# 002-main.net
KiCad netlist of a schematic drawn in EAGLE
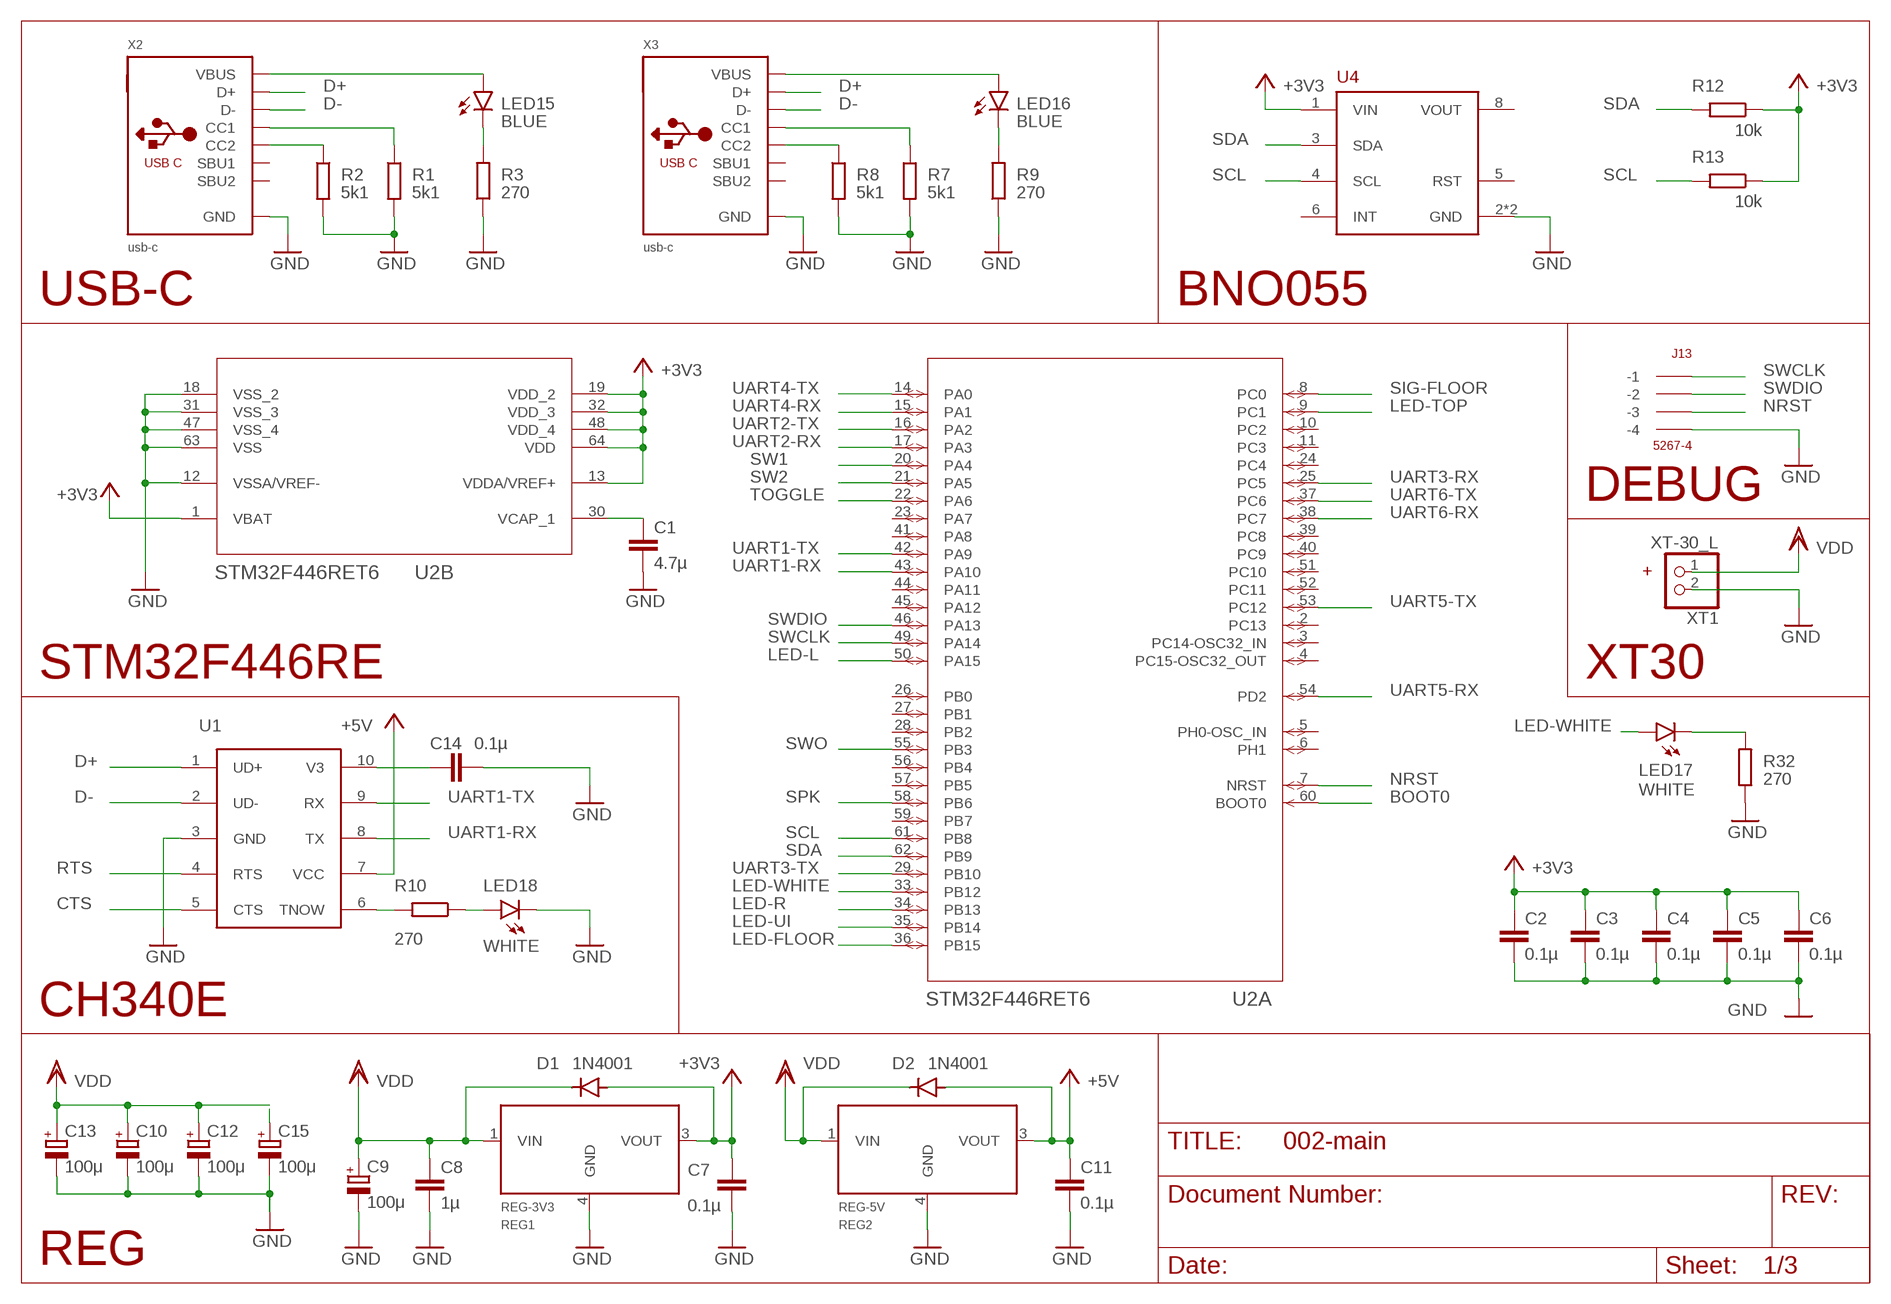
[diagram p0: schematic, sheet 1]
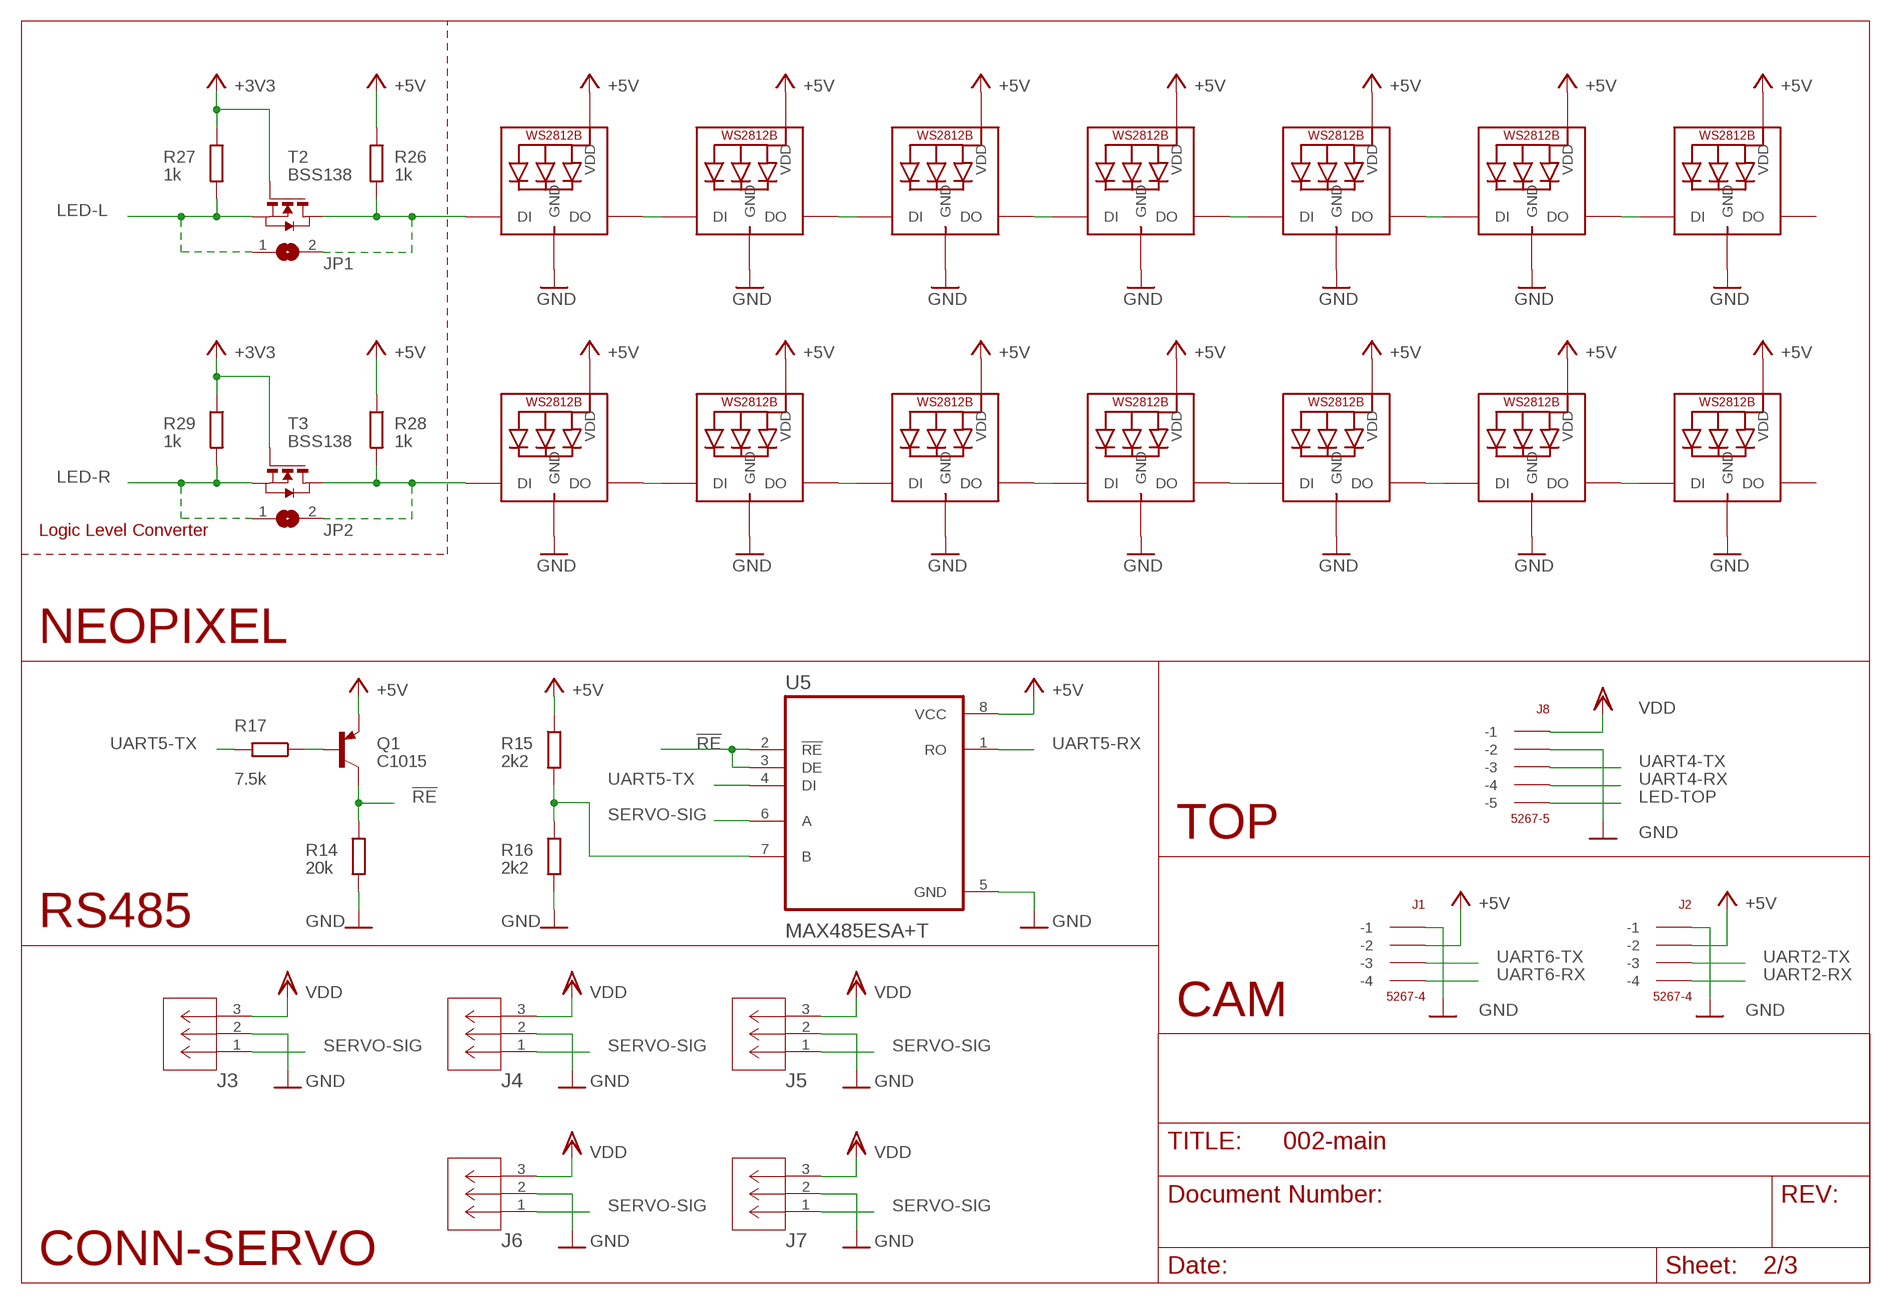
[diagram p1: schematic, sheet 2]
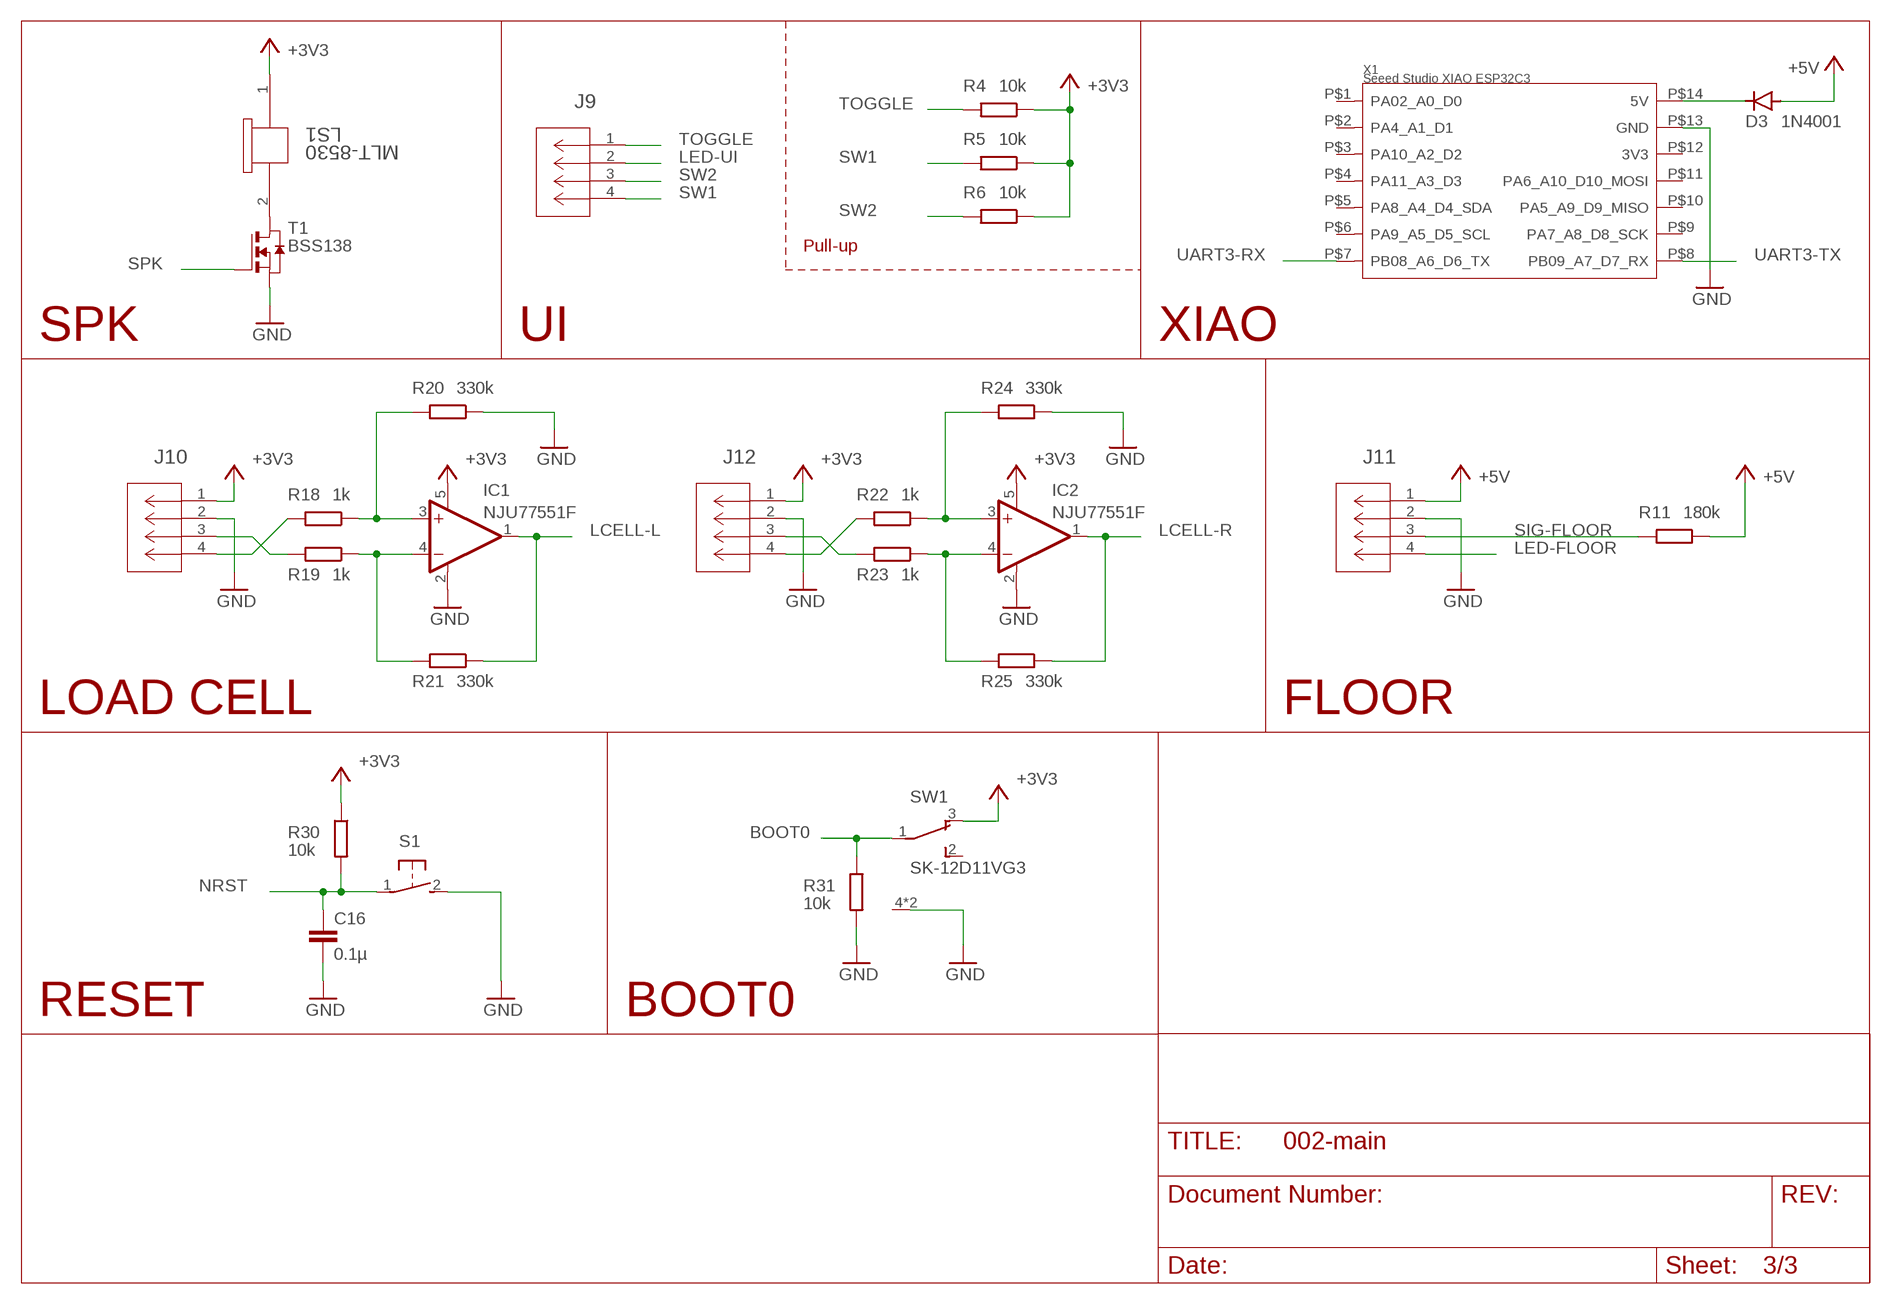
[diagram p2: schematic, sheet 3]

(export (version "E")
  (design (tool "Eeschema 10.0.6"))
  (components
    (comp (ref "C1")
      (value "4.7µ")
      (footprint "eagle-import:C0603")
      (libsource (lib "eagle-import") (part "C-EUC0603"))
    )
    (comp (ref "C2")
      (value "0.1µ")
      (footprint "eagle-import:C0603")
      (libsource (lib "eagle-import") (part "C-EUC0603"))
    )
    (comp (ref "C3")
      (value "0.1µ")
      (footprint "eagle-import:C0603")
      (libsource (lib "eagle-import") (part "C-EUC0603"))
    )
    (comp (ref "C4")
      (value "0.1µ")
      (footprint "eagle-import:C0603")
      (libsource (lib "eagle-import") (part "C-EUC0603"))
    )
    (comp (ref "C5")
      (value "0.1µ")
      (footprint "eagle-import:C0603")
      (libsource (lib "eagle-import") (part "C-EUC0603"))
    )
    (comp (ref "C6")
      (value "0.1µ")
      (footprint "eagle-import:C0603")
      (libsource (lib "eagle-import") (part "C-EUC0603"))
    )
    (comp (ref "C7")
      (value "0.1µ")
      (footprint "eagle-import:C0603")
      (libsource (lib "eagle-import") (part "C-EUC0603"))
    )
    (comp (ref "C8")
      (value "1µ")
      (footprint "eagle-import:C0603")
      (libsource (lib "eagle-import") (part "C-EUC0603"))
    )
    (comp (ref "C9")
      (value "100μ")
      (footprint "eagle-import:153CLV-0505")
      (libsource (lib "eagle-import") (part "CPOL-EU153CLV-0505"))
    )
    (comp (ref "C10")
      (value "100μ")
      (footprint "eagle-import:153CLV-0505")
      (libsource (lib "eagle-import") (part "CPOL-EU153CLV-0505"))
    )
    (comp (ref "C11")
      (value "0.1µ")
      (footprint "eagle-import:C0603")
      (libsource (lib "eagle-import") (part "C-EUC0603"))
    )
    (comp (ref "C12")
      (value "100μ")
      (footprint "eagle-import:153CLV-0505")
      (libsource (lib "eagle-import") (part "CPOL-EU153CLV-0505"))
    )
    (comp (ref "C13")
      (value "100μ")
      (footprint "eagle-import:153CLV-0505")
      (libsource (lib "eagle-import") (part "CPOL-EU153CLV-0505"))
    )
    (comp (ref "C14")
      (value "0.1µ")
      (footprint "eagle-import:C0603")
      (libsource (lib "eagle-import") (part "C-EUC0603"))
    )
    (comp (ref "C15")
      (value "100μ")
      (footprint "eagle-import:153CLV-0505")
      (libsource (lib "eagle-import") (part "CPOL-EU153CLV-0505"))
    )
    (comp (ref "D1")
      (value "1N4001")
      (footprint "eagle-import:SMA-DO214AC")
      (libsource (lib "eagle-import") (part "GF1"))
    )
    (comp (ref "D2")
      (value "1N4001")
      (footprint "eagle-import:SMA-DO214AC")
      (libsource (lib "eagle-import") (part "GF1"))
    )
    (comp (ref "J13")
      (value "5267-4")
      (footprint "eagle-import:5267-4")
      (libsource (lib "eagle-import") (part "5267-4"))
    )
    (comp (ref "LED15")
      (value "BLUE")
      (footprint "eagle-import:SML0603")
      (libsource (lib "eagle-import") (part "LEDSML0603"))
    )
    (comp (ref "LED16")
      (value "BLUE")
      (footprint "eagle-import:SML0603")
      (libsource (lib "eagle-import") (part "LEDSML0603"))
    )
    (comp (ref "LED17")
      (value "WHITE")
      (footprint "eagle-import:SML0603")
      (libsource (lib "eagle-import") (part "LEDSML0603"))
    )
    (comp (ref "LED18")
      (value "WHITE")
      (footprint "eagle-import:SML0603")
      (libsource (lib "eagle-import") (part "LEDSML0603"))
    )
    (comp (ref "R1")
      (value "5k1")
      (footprint "eagle-import:R0402")
      (libsource (lib "eagle-import") (part "R-EU_R0402"))
    )
    (comp (ref "R2")
      (value "5k1")
      (footprint "eagle-import:R0402")
      (libsource (lib "eagle-import") (part "R-EU_R0402"))
    )
    (comp (ref "R3")
      (value "270")
      (footprint "eagle-import:R0402")
      (libsource (lib "eagle-import") (part "R-EU_R0402"))
    )
    (comp (ref "R7")
      (value "5k1")
      (footprint "eagle-import:R0402")
      (libsource (lib "eagle-import") (part "R-EU_R0402"))
    )
    (comp (ref "R8")
      (value "5k1")
      (footprint "eagle-import:R0402")
      (libsource (lib "eagle-import") (part "R-EU_R0402"))
    )
    (comp (ref "R9")
      (value "270")
      (footprint "eagle-import:R0402")
      (libsource (lib "eagle-import") (part "R-EU_R0402"))
    )
    (comp (ref "R10")
      (value "270")
      (footprint "eagle-import:R0402")
      (libsource (lib "eagle-import") (part "R-EU_R0402"))
    )
    (comp (ref "R12")
      (value "10k")
      (footprint "eagle-import:R0402")
      (libsource (lib "eagle-import") (part "R-EU_R0402"))
    )
    (comp (ref "R13")
      (value "10k")
      (footprint "eagle-import:R0402")
      (libsource (lib "eagle-import") (part "R-EU_R0402"))
    )
    (comp (ref "R32")
      (value "270")
      (footprint "eagle-import:R0402")
      (libsource (lib "eagle-import") (part "R-EU_R0402"))
    )
    (comp (ref "REG1")
      (value "REG-3V3")
      (footprint "eagle-import:MYPARTS_D-PAK_TO252AA")
      (libsource (lib "eagle-import") (part "MYPARTS_NJM7800S-REGULATOR"))
    )
    (comp (ref "REG2")
      (value "REG-5V")
      (footprint "eagle-import:MYPARTS_D-PAK_TO252AA")
      (libsource (lib "eagle-import") (part "MYPARTS_NJM7800S-REGULATOR"))
    )
    (comp (ref "U1")
      (value "CH340ESMD")
      (footprint "eagle-import:MSOP10")
      (libsource (lib "eagle-import") (part "CH340ESMD"))
    )
    (comp (ref "U2")
      (value "STM32F446RET6")
      (footprint "eagle-import:LQFP64-10X10MM")
      (fields (field (name "COPYRIGHT") "Copyright (C) 2022 Ultra Librarian. All rights reserved."))
      (libsource (lib "eagle-import") (part "STM32F446RET6"))
    )
    (comp (ref "U4")
      (value "BNO055")
      (footprint "eagle-import:SOCKET-08")
      (libsource (lib "eagle-import") (part "BNO055"))
    )
    (comp (ref "X2")
      (value "usb-c")
      (footprint "eagle-import:USB_C_CUSB31-CFM2AX-01-X")
      (libsource (lib "eagle-import") (part "USB_C"))
    )
    (comp (ref "X3")
      (value "usb-c")
      (footprint "eagle-import:USB_C_CUSB31-CFM2AX-01-X")
      (libsource (lib "eagle-import") (part "USB_C"))
    )
    (comp (ref "XT1")
      (value "XT-30_L")
      (footprint "eagle-import:XT-30_L")
      (libsource (lib "eagle-import") (part "XT-30_L"))
    )
    (comp (ref "J1")
      (value "5267-4")
      (footprint "eagle-import:5267-4")
      (libsource (lib "eagle-import") (part "5267-4"))
    )
    (comp (ref "J2")
      (value "5267-4")
      (footprint "eagle-import:5267-4")
      (libsource (lib "eagle-import") (part "5267-4"))
    )
    (comp (ref "J3")
      (value "22057035")
      (footprint "eagle-import:CON_22057035_MOL")
      (fields (field (name "COPYRIGHT") "Copyright (C) 2022 Ultra Librarian. All rights reserved."))
      (libsource (lib "eagle-import") (part "22057035"))
    )
    (comp (ref "J4")
      (value "22057035")
      (footprint "eagle-import:CON_22057035_MOL")
      (fields (field (name "COPYRIGHT") "Copyright (C) 2022 Ultra Librarian. All rights reserved."))
      (libsource (lib "eagle-import") (part "22057035"))
    )
    (comp (ref "J5")
      (value "22057035")
      (footprint "eagle-import:CON_22057035_MOL")
      (fields (field (name "COPYRIGHT") "Copyright (C) 2022 Ultra Librarian. All rights reserved."))
      (libsource (lib "eagle-import") (part "22057035"))
    )
    (comp (ref "J6")
      (value "22057035")
      (footprint "eagle-import:CON_22057035_MOL")
      (fields (field (name "COPYRIGHT") "Copyright (C) 2022 Ultra Librarian. All rights reserved."))
      (libsource (lib "eagle-import") (part "22057035"))
    )
    (comp (ref "J7")
      (value "22057035")
      (footprint "eagle-import:CON_22057035_MOL")
      (fields (field (name "COPYRIGHT") "Copyright (C) 2022 Ultra Librarian. All rights reserved."))
      (libsource (lib "eagle-import") (part "22057035"))
    )
    (comp (ref "J8")
      (value "5267-5")
      (footprint "eagle-import:5267-5")
      (libsource (lib "eagle-import") (part "5267-5"))
    )
    (comp (ref "JP1")
      (value "JP2")
      (footprint "eagle-import:JP2")
      (libsource (lib "eagle-import") (part "JP2"))
    )
    (comp (ref "JP2")
      (value "JP2")
      (footprint "eagle-import:JP2")
      (libsource (lib "eagle-import") (part "JP2"))
    )
    (comp (ref "LED1")
      (value "WS2812B_2020")
      (footprint "eagle-import:WS2812B_2020")
      (libsource (lib "eagle-import") (part "WS2812B_2020"))
    )
    (comp (ref "LED2")
      (value "WS2812B_2020")
      (footprint "eagle-import:WS2812B_2020")
      (libsource (lib "eagle-import") (part "WS2812B_2020"))
    )
    (comp (ref "LED3")
      (value "WS2812B_2020")
      (footprint "eagle-import:WS2812B_2020")
      (libsource (lib "eagle-import") (part "WS2812B_2020"))
    )
    (comp (ref "LED4")
      (value "WS2812B_2020")
      (footprint "eagle-import:WS2812B_2020")
      (libsource (lib "eagle-import") (part "WS2812B_2020"))
    )
    (comp (ref "LED5")
      (value "WS2812B_2020")
      (footprint "eagle-import:WS2812B_2020")
      (libsource (lib "eagle-import") (part "WS2812B_2020"))
    )
    (comp (ref "LED6")
      (value "WS2812B_2020")
      (footprint "eagle-import:WS2812B_2020")
      (libsource (lib "eagle-import") (part "WS2812B_2020"))
    )
    (comp (ref "LED7")
      (value "WS2812B_2020")
      (footprint "eagle-import:WS2812B_2020")
      (libsource (lib "eagle-import") (part "WS2812B_2020"))
    )
    (comp (ref "LED8")
      (value "WS2812B_2020")
      (footprint "eagle-import:WS2812B_2020")
      (libsource (lib "eagle-import") (part "WS2812B_2020"))
    )
    (comp (ref "LED9")
      (value "WS2812B_2020")
      (footprint "eagle-import:WS2812B_2020")
      (libsource (lib "eagle-import") (part "WS2812B_2020"))
    )
    (comp (ref "LED10")
      (value "WS2812B_2020")
      (footprint "eagle-import:WS2812B_2020")
      (libsource (lib "eagle-import") (part "WS2812B_2020"))
    )
    (comp (ref "LED11")
      (value "WS2812B_2020")
      (footprint "eagle-import:WS2812B_2020")
      (libsource (lib "eagle-import") (part "WS2812B_2020"))
    )
    (comp (ref "LED12")
      (value "WS2812B_2020")
      (footprint "eagle-import:WS2812B_2020")
      (libsource (lib "eagle-import") (part "WS2812B_2020"))
    )
    (comp (ref "LED13")
      (value "WS2812B_2020")
      (footprint "eagle-import:WS2812B_2020")
      (libsource (lib "eagle-import") (part "WS2812B_2020"))
    )
    (comp (ref "LED14")
      (value "WS2812B_2020")
      (footprint "eagle-import:WS2812B_2020")
      (libsource (lib "eagle-import") (part "WS2812B_2020"))
    )
    (comp (ref "Q1")
      (value "C1015")
      (footprint "eagle-import:SOT23")
      (libsource (lib "eagle-import") (part "BCX71SMD"))
    )
    (comp (ref "R14")
      (value "20k")
      (footprint "eagle-import:R0402")
      (libsource (lib "eagle-import") (part "R-EU_R0402"))
    )
    (comp (ref "R15")
      (value "2k2")
      (footprint "eagle-import:R0402")
      (libsource (lib "eagle-import") (part "R-EU_R0402"))
    )
    (comp (ref "R16")
      (value "2k2")
      (footprint "eagle-import:R0402")
      (libsource (lib "eagle-import") (part "R-EU_R0402"))
    )
    (comp (ref "R17")
      (value "7.5k")
      (footprint "eagle-import:R0402")
      (libsource (lib "eagle-import") (part "R-EU_R0402"))
    )
    (comp (ref "R26")
      (value "1k")
      (footprint "eagle-import:R0402")
      (libsource (lib "eagle-import") (part "R-EU_R0402"))
    )
    (comp (ref "R27")
      (value "1k")
      (footprint "eagle-import:R0402")
      (libsource (lib "eagle-import") (part "R-EU_R0402"))
    )
    (comp (ref "R28")
      (value "1k")
      (footprint "eagle-import:R0402")
      (libsource (lib "eagle-import") (part "R-EU_R0402"))
    )
    (comp (ref "R29")
      (value "1k")
      (footprint "eagle-import:R0402")
      (libsource (lib "eagle-import") (part "R-EU_R0402"))
    )
    (comp (ref "T2")
      (value "BSS138")
      (footprint "eagle-import:SOT-23")
      (libsource (lib "eagle-import") (part "NMOSSOT23"))
    )
    (comp (ref "T3")
      (value "BSS138")
      (footprint "eagle-import:SOT-23")
      (libsource (lib "eagle-import") (part "NMOSSOT23"))
    )
    (comp (ref "U5")
      (value "MAX485ESA+T")
      (footprint "eagle-import:SOIC127P600X175-8N")
      (fields (field (name "MF") "Maxim Integrated") (field (name "MP") "MAX485ESA"))
      (libsource (lib "eagle-import") (part "MAX485ESA+T"))
    )
    (comp (ref "C16")
      (value "0.1µ")
      (footprint "eagle-import:C0603")
      (libsource (lib "eagle-import") (part "C-EUC0603"))
    )
    (comp (ref "D3")
      (value "1N4001")
      (footprint "eagle-import:SMA-DO214AC")
      (libsource (lib "eagle-import") (part "GF1"))
    )
    (comp (ref "IC1")
      (value "NJU77551F")
      (footprint "eagle-import:SOT23-5")
      (fields (field (name "MPN") "OPA340NA/3KG4"))
      (libsource (lib "eagle-import") (part "OPA340N"))
    )
    (comp (ref "IC2")
      (value "NJU77551F")
      (footprint "eagle-import:SOT23-5")
      (fields (field (name "MPN") "OPA340NA/3KG4"))
      (libsource (lib "eagle-import") (part "OPA340N"))
    )
    (comp (ref "J9")
      (value "22057045")
      (footprint "eagle-import:CON_22057045_MOL")
      (fields (field (name "COPYRIGHT") "Copyright (C) 2022 Ultra Librarian. All rights reserved."))
      (libsource (lib "eagle-import") (part "22057045"))
    )
    (comp (ref "J10")
      (value "22057045")
      (footprint "eagle-import:CON_22057045_MOL")
      (fields (field (name "COPYRIGHT") "Copyright (C) 2022 Ultra Librarian. All rights reserved."))
      (libsource (lib "eagle-import") (part "22057045"))
    )
    (comp (ref "J11")
      (value "22057045")
      (footprint "eagle-import:CON_22057045_MOL")
      (fields (field (name "COPYRIGHT") "Copyright (C) 2022 Ultra Librarian. All rights reserved."))
      (libsource (lib "eagle-import") (part "22057045"))
    )
    (comp (ref "J12")
      (value "22057045")
      (footprint "eagle-import:CON_22057045_MOL")
      (fields (field (name "COPYRIGHT") "Copyright (C) 2022 Ultra Librarian. All rights reserved."))
      (libsource (lib "eagle-import") (part "22057045"))
    )
    (comp (ref "LS1")
      (value "MLT-8530")
      (footprint "eagle-import:MLT-8530_JHE")
      (fields (field (name "COPYRIGHT") "Copyright (C) 2022 Ultra Librarian. All rights reserved."))
      (libsource (lib "eagle-import") (part "MLT-8530"))
    )
    (comp (ref "R4")
      (value "10k")
      (footprint "eagle-import:R0402")
      (libsource (lib "eagle-import") (part "R-EU_R0402"))
    )
    (comp (ref "R5")
      (value "10k")
      (footprint "eagle-import:R0402")
      (libsource (lib "eagle-import") (part "R-EU_R0402"))
    )
    (comp (ref "R6")
      (value "10k")
      (footprint "eagle-import:R0402")
      (libsource (lib "eagle-import") (part "R-EU_R0402"))
    )
    (comp (ref "R11")
      (value "180k")
      (footprint "eagle-import:R0402")
      (libsource (lib "eagle-import") (part "R-EU_R0402"))
    )
    (comp (ref "R18")
      (value "1k")
      (footprint "eagle-import:R0402")
      (libsource (lib "eagle-import") (part "R-EU_R0402"))
    )
    (comp (ref "R19")
      (value "1k")
      (footprint "eagle-import:R0402")
      (libsource (lib "eagle-import") (part "R-EU_R0402"))
    )
    (comp (ref "R20")
      (value "330k")
      (footprint "eagle-import:R0402")
      (libsource (lib "eagle-import") (part "R-EU_R0402"))
    )
    (comp (ref "R21")
      (value "330k")
      (footprint "eagle-import:R0402")
      (libsource (lib "eagle-import") (part "R-EU_R0402"))
    )
    (comp (ref "R22")
      (value "1k")
      (footprint "eagle-import:R0402")
      (libsource (lib "eagle-import") (part "R-EU_R0402"))
    )
    (comp (ref "R23")
      (value "1k")
      (footprint "eagle-import:R0402")
      (libsource (lib "eagle-import") (part "R-EU_R0402"))
    )
    (comp (ref "R24")
      (value "330k")
      (footprint "eagle-import:R0402")
      (libsource (lib "eagle-import") (part "R-EU_R0402"))
    )
    (comp (ref "R25")
      (value "330k")
      (footprint "eagle-import:R0402")
      (libsource (lib "eagle-import") (part "R-EU_R0402"))
    )
    (comp (ref "R30")
      (value "10k")
      (footprint "eagle-import:R0402")
      (libsource (lib "eagle-import") (part "R-EU_R0402"))
    )
    (comp (ref "R31")
      (value "10k")
      (footprint "eagle-import:R0402")
      (libsource (lib "eagle-import") (part "R-EU_R0402"))
    )
    (comp (ref "S1")
      (value "31-XX")
      (footprint "eagle-import:B3F-31XX")
      (fields (field (name "MPN") "B3F-3100"))
      (libsource (lib "eagle-import") (part "31-XX"))
    )
    (comp (ref "SW1")
      (value "SK-12D11VG3")
      (footprint "eagle-import:SK-12D11VG3")
      (libsource (lib "eagle-import") (part "SK-12D11VG3"))
    )
    (comp (ref "T1")
      (value "BSS138")
      (footprint "eagle-import:SOT-23")
      (libsource (lib "eagle-import") (part "NMOSSOT23"))
    )
    (comp (ref "X1")
      (value "Seeed Studio XIAO ESP32C3")
      (footprint "eagle-import:XIAO-PINHEAD")
      (libsource (lib "eagle-import") (part "SEEEDUINO-XIAO-DIP"))
    )
  )
  (nets
    (net (code "1") (name "+3V3") (class "Default")
      (node (ref "C2") (pin "1") (pinfunction "1_1") (pintype "passive"))
      (node (ref "C3") (pin "1") (pinfunction "1_1") (pintype "passive"))
      (node (ref "C4") (pin "1") (pinfunction "1_1") (pintype "passive"))
      (node (ref "C5") (pin "1") (pinfunction "1_1") (pintype "passive"))
      (node (ref "C6") (pin "1") (pinfunction "1_1") (pintype "passive"))
      (node (ref "C7") (pin "1") (pinfunction "1_1") (pintype "passive"))
      (node (ref "D1") (pin "A") (pinfunction "A_A") (pintype "passive"))
      (node (ref "IC1") (pin "5") (pinfunction "V+_5") (pintype "power_in"))
      (node (ref "IC2") (pin "5") (pinfunction "V+_5") (pintype "power_in"))
      (node (ref "J10") (pin "1") (pinfunction "1_1") (pintype "passive"))
      (node (ref "J12") (pin "1") (pinfunction "1_1") (pintype "passive"))
      (node (ref "LS1") (pin "1") (pinfunction "1_1") (pintype "passive"))
      (node (ref "R12") (pin "1") (pinfunction "1_1") (pintype "passive"))
      (node (ref "R13") (pin "1") (pinfunction "1_1") (pintype "passive"))
      (node (ref "R27") (pin "1") (pinfunction "1_1") (pintype "passive"))
      (node (ref "R29") (pin "1") (pinfunction "1_1") (pintype "passive"))
      (node (ref "R30") (pin "1") (pinfunction "1_1") (pintype "passive"))
      (node (ref "R4") (pin "1") (pinfunction "1_1") (pintype "passive"))
      (node (ref "R5") (pin "1") (pinfunction "1_1") (pintype "passive"))
      (node (ref "R6") (pin "1") (pinfunction "1_1") (pintype "passive"))
      (node (ref "REG1") (pin "3") (pinfunction "VOUT_3") (pintype "passive"))
      (node (ref "SW1") (pin "3") (pinfunction "O_3") (pintype "passive"))
      (node (ref "T2") (pin "3") (pinfunction "G_3") (pintype "passive"))
      (node (ref "T3") (pin "3") (pinfunction "G_3") (pintype "passive"))
      (node (ref "U2") (pin "1") (pinfunction "VBAT_1") (pintype "power_in"))
      (node (ref "U2") (pin "13") (pinfunction "VDDA/VREF+_13") (pintype "power_in"))
      (node (ref "U2") (pin "19") (pinfunction "VDD_2_19") (pintype "power_in"))
      (node (ref "U2") (pin "32") (pinfunction "VDD_3_32") (pintype "power_in"))
      (node (ref "U2") (pin "48") (pinfunction "VDD_4_48") (pintype "power_in"))
      (node (ref "U2") (pin "64") (pinfunction "VDD_64") (pintype "power_in"))
      (node (ref "U4") (pin "1") (pinfunction "VIN_1") (pintype "power_in"))
    )
    (net (code "2") (name "+5V") (class "Default")
      (node (ref "C11") (pin "1") (pinfunction "1_1") (pintype "passive"))
      (node (ref "D2") (pin "A") (pinfunction "A_A") (pintype "passive"))
      (node (ref "D3") (pin "A") (pinfunction "A_A") (pintype "passive"))
      (node (ref "J1") (pin "P$2") (pinfunction "-2_P$2") (pintype "bidirectional"))
      (node (ref "J11") (pin "1") (pinfunction "1_1") (pintype "passive"))
      (node (ref "J2") (pin "P$2") (pinfunction "-2_P$2") (pintype "bidirectional"))
      (node (ref "LED1") (pin "4") (pinfunction "VDD_4") (pintype "power_in"))
      (node (ref "LED10") (pin "4") (pinfunction "VDD_4") (pintype "power_in"))
      (node (ref "LED11") (pin "4") (pinfunction "VDD_4") (pintype "power_in"))
      (node (ref "LED12") (pin "4") (pinfunction "VDD_4") (pintype "power_in"))
      (node (ref "LED13") (pin "4") (pinfunction "VDD_4") (pintype "power_in"))
      (node (ref "LED14") (pin "4") (pinfunction "VDD_4") (pintype "power_in"))
      (node (ref "LED2") (pin "4") (pinfunction "VDD_4") (pintype "power_in"))
      (node (ref "LED3") (pin "4") (pinfunction "VDD_4") (pintype "power_in"))
      (node (ref "LED4") (pin "4") (pinfunction "VDD_4") (pintype "power_in"))
      (node (ref "LED5") (pin "4") (pinfunction "VDD_4") (pintype "power_in"))
      (node (ref "LED6") (pin "4") (pinfunction "VDD_4") (pintype "power_in"))
      (node (ref "LED7") (pin "4") (pinfunction "VDD_4") (pintype "power_in"))
      (node (ref "LED8") (pin "4") (pinfunction "VDD_4") (pintype "power_in"))
      (node (ref "LED9") (pin "4") (pinfunction "VDD_4") (pintype "power_in"))
      (node (ref "Q1") (pin "2") (pinfunction "E_2") (pintype "passive"))
      (node (ref "R11") (pin "1") (pinfunction "1_1") (pintype "passive"))
      (node (ref "R15") (pin "1") (pinfunction "1_1") (pintype "passive"))
      (node (ref "R26") (pin "1") (pinfunction "1_1") (pintype "passive"))
      (node (ref "R28") (pin "1") (pinfunction "1_1") (pintype "passive"))
      (node (ref "REG2") (pin "3") (pinfunction "VOUT_3") (pintype "passive"))
      (node (ref "U1") (pin "7") (pinfunction "VCC_7") (pintype "power_in"))
      (node (ref "U5") (pin "8") (pinfunction "VCC_8") (pintype "power_in"))
    )
    (net (code "3") (name "BOOT0") (class "Default")
      (node (ref "R31") (pin "1") (pinfunction "1_1") (pintype "passive"))
      (node (ref "SW1") (pin "1") (pinfunction "P_1") (pintype "passive"))
      (node (ref "U2") (pin "60") (pinfunction "BOOT0_60") (pintype "input"))
    )
    (net (code "4") (name "CTS") (class "Default")
      (node (ref "U1") (pin "5") (pinfunction "CTS_5") (pintype "input"))
    )
    (net (code "5") (name "D+") (class "Default")
      (node (ref "U1") (pin "1") (pinfunction "UD+_1") (pintype "bidirectional"))
      (node (ref "X2") (pin "A6") (pinfunction "D+_A6") (pintype "bidirectional"))
      (node (ref "X2") (pin "B6") (pinfunction "D+_B6") (pintype "bidirectional"))
      (node (ref "X3") (pin "A6") (pinfunction "D+_A6") (pintype "bidirectional"))
      (node (ref "X3") (pin "B6") (pinfunction "D+_B6") (pintype "bidirectional"))
    )
    (net (code "6") (name "D-") (class "Default")
      (node (ref "U1") (pin "2") (pinfunction "UD-_2") (pintype "bidirectional"))
      (node (ref "X2") (pin "A7") (pinfunction "D-_A7") (pintype "bidirectional"))
      (node (ref "X2") (pin "B7") (pinfunction "D-_B7") (pintype "bidirectional"))
      (node (ref "X3") (pin "A7") (pinfunction "D-_A7") (pintype "bidirectional"))
      (node (ref "X3") (pin "B7") (pinfunction "D-_B7") (pintype "bidirectional"))
    )
    (net (code "7") (name "GND") (class "Default")
      (node (ref "C1") (pin "2") (pinfunction "2_2") (pintype "passive"))
      (node (ref "C10") (pin "-") (pinfunction "-_-") (pintype "passive"))
      (node (ref "C11") (pin "2") (pinfunction "2_2") (pintype "passive"))
      (node (ref "C12") (pin "-") (pinfunction "-_-") (pintype "passive"))
      (node (ref "C13") (pin "-") (pinfunction "-_-") (pintype "passive"))
      (node (ref "C14") (pin "2") (pinfunction "2_2") (pintype "passive"))
      (node (ref "C15") (pin "-") (pinfunction "-_-") (pintype "passive"))
      (node (ref "C16") (pin "2") (pinfunction "2_2") (pintype "passive"))
      (node (ref "C2") (pin "2") (pinfunction "2_2") (pintype "passive"))
      (node (ref "C3") (pin "2") (pinfunction "2_2") (pintype "passive"))
      (node (ref "C4") (pin "2") (pinfunction "2_2") (pintype "passive"))
      (node (ref "C5") (pin "2") (pinfunction "2_2") (pintype "passive"))
      (node (ref "C6") (pin "2") (pinfunction "2_2") (pintype "passive"))
      (node (ref "C7") (pin "2") (pinfunction "2_2") (pintype "passive"))
      (node (ref "C8") (pin "2") (pinfunction "2_2") (pintype "passive"))
      (node (ref "C9") (pin "-") (pinfunction "-_-") (pintype "passive"))
      (node (ref "IC1") (pin "2") (pinfunction "V-_2") (pintype "power_in"))
      (node (ref "IC2") (pin "2") (pinfunction "V-_2") (pintype "power_in"))
      (node (ref "J1") (pin "P$1") (pinfunction "-1_P$1") (pintype "bidirectional"))
      (node (ref "J10") (pin "2") (pinfunction "2_2") (pintype "passive"))
      (node (ref "J11") (pin "2") (pinfunction "2_2") (pintype "passive"))
      (node (ref "J12") (pin "2") (pinfunction "2_2") (pintype "passive"))
      (node (ref "J13") (pin "P$4") (pinfunction "-4_P$4") (pintype "bidirectional"))
      (node (ref "J2") (pin "P$1") (pinfunction "-1_P$1") (pintype "bidirectional"))
      (node (ref "J3") (pin "2") (pinfunction "2_2") (pintype "passive"))
      (node (ref "J4") (pin "2") (pinfunction "2_2") (pintype "passive"))
      (node (ref "J5") (pin "2") (pinfunction "2_2") (pintype "passive"))
      (node (ref "J6") (pin "2") (pinfunction "2_2") (pintype "passive"))
      (node (ref "J7") (pin "2") (pinfunction "2_2") (pintype "passive"))
      (node (ref "J8") (pin "P$2") (pinfunction "-2_P$2") (pintype "bidirectional"))
      (node (ref "LED1") (pin "2") (pinfunction "GND_2") (pintype "power_in"))
      (node (ref "LED10") (pin "2") (pinfunction "GND_2") (pintype "power_in"))
      (node (ref "LED11") (pin "2") (pinfunction "GND_2") (pintype "power_in"))
      (node (ref "LED12") (pin "2") (pinfunction "GND_2") (pintype "power_in"))
      (node (ref "LED13") (pin "2") (pinfunction "GND_2") (pintype "power_in"))
      (node (ref "LED14") (pin "2") (pinfunction "GND_2") (pintype "power_in"))
      (node (ref "LED18") (pin "C") (pinfunction "C_C") (pintype "passive"))
      (node (ref "LED2") (pin "2") (pinfunction "GND_2") (pintype "power_in"))
      (node (ref "LED3") (pin "2") (pinfunction "GND_2") (pintype "power_in"))
      (node (ref "LED4") (pin "2") (pinfunction "GND_2") (pintype "power_in"))
      (node (ref "LED5") (pin "2") (pinfunction "GND_2") (pintype "power_in"))
      (node (ref "LED6") (pin "2") (pinfunction "GND_2") (pintype "power_in"))
      (node (ref "LED7") (pin "2") (pinfunction "GND_2") (pintype "power_in"))
      (node (ref "LED8") (pin "2") (pinfunction "GND_2") (pintype "power_in"))
      (node (ref "LED9") (pin "2") (pinfunction "GND_2") (pintype "power_in"))
      (node (ref "R1") (pin "2") (pinfunction "2_2") (pintype "passive"))
      (node (ref "R14") (pin "2") (pinfunction "2_2") (pintype "passive"))
      (node (ref "R16") (pin "2") (pinfunction "2_2") (pintype "passive"))
      (node (ref "R2") (pin "2") (pinfunction "2_2") (pintype "passive"))
      (node (ref "R20") (pin "1") (pinfunction "1_1") (pintype "passive"))
      (node (ref "R24") (pin "1") (pinfunction "1_1") (pintype "passive"))
      (node (ref "R3") (pin "1") (pinfunction "1_1") (pintype "passive"))
      (node (ref "R31") (pin "2") (pinfunction "2_2") (pintype "passive"))
      (node (ref "R32") (pin "1") (pinfunction "1_1") (pintype "passive"))
      (node (ref "R7") (pin "2") (pinfunction "2_2") (pintype "passive"))
      (node (ref "R8") (pin "2") (pinfunction "2_2") (pintype "passive"))
      (node (ref "R9") (pin "1") (pinfunction "1_1") (pintype "passive"))
      (node (ref "REG1") (pin "4") (pinfunction "GND_4") (pintype "passive"))
      (node (ref "REG2") (pin "4") (pinfunction "GND_4") (pintype "passive"))
      (node (ref "S1") (pin "2") (pinfunction "S_2") (pintype "passive"))
      (node (ref "SW1") (pin "4") (pinfunction "CASE_4") (pintype "bidirectional"))
      (node (ref "SW1") (pin "5") (pinfunction "CASE_5") (pintype "bidirectional"))
      (node (ref "T1") (pin "2") (pinfunction "S_2") (pintype "passive"))
      (node (ref "U1") (pin "3") (pinfunction "GND_3") (pintype "power_in"))
      (node (ref "U2") (pin "12") (pinfunction "VSSA/VREF-_12") (pintype "power_in"))
      (node (ref "U2") (pin "18") (pinfunction "VSS_2_18") (pintype "power_in"))
      (node (ref "U2") (pin "31") (pinfunction "VSS_3_31") (pintype "power_in"))
      (node (ref "U2") (pin "47") (pinfunction "VSS_4_47") (pintype "power_in"))
      (node (ref "U2") (pin "63") (pinfunction "VSS_63") (pintype "power_in"))
      (node (ref "U4") (pin "2") (pinfunction "GND_2") (pintype "power_in"))
      (node (ref "U4") (pin "7") (pinfunction "GND_7") (pintype "power_in"))
      (node (ref "U5") (pin "5") (pinfunction "GND_5") (pintype "power_in"))
      (node (ref "X1") (pin "P$13") (pinfunction "GND_P$13") (pintype "bidirectional"))
      (node (ref "X2") (pin "A1B12") (pinfunction "GND_A1B12") (pintype "power_in"))
      (node (ref "X2") (pin "B1A12") (pinfunction "GND_B1A12") (pintype "power_in"))
      (node (ref "X3") (pin "A1B12") (pinfunction "GND_A1B12") (pintype "power_in"))
      (node (ref "X3") (pin "B1A12") (pinfunction "GND_B1A12") (pintype "power_in"))
      (node (ref "XT1") (pin "2") (pinfunction "2_2") (pintype "passive"))
    )
    (net (code "8") (name "LCELL-L") (class "Default")
      (node (ref "IC1") (pin "1") (pinfunction "OUT_1") (pintype "output"))
      (node (ref "R21") (pin "1") (pinfunction "1_1") (pintype "passive"))
    )
    (net (code "9") (name "LCELL-R") (class "Default")
      (node (ref "IC2") (pin "1") (pinfunction "OUT_1") (pintype "output"))
      (node (ref "R25") (pin "1") (pinfunction "1_1") (pintype "passive"))
    )
    (net (code "10") (name "LED-FLOOR") (class "Default")
      (node (ref "J11") (pin "4") (pinfunction "4_4") (pintype "passive"))
      (node (ref "U2") (pin "36") (pinfunction "PB15_36") (pintype "bidirectional"))
    )
    (net (code "11") (name "LED-L") (class "Default")
      (node (ref "JP1") (pin "1") (pinfunction "1_1") (pintype "passive"))
      (node (ref "R27") (pin "2") (pinfunction "2_2") (pintype "passive"))
      (node (ref "T2") (pin "2") (pinfunction "S_2") (pintype "passive"))
      (node (ref "U2") (pin "50") (pinfunction "PA15_50") (pintype "bidirectional"))
    )
    (net (code "12") (name "LED-R") (class "Default")
      (node (ref "JP2") (pin "1") (pinfunction "1_1") (pintype "passive"))
      (node (ref "R29") (pin "2") (pinfunction "2_2") (pintype "passive"))
      (node (ref "T3") (pin "2") (pinfunction "S_2") (pintype "passive"))
      (node (ref "U2") (pin "34") (pinfunction "PB13_34") (pintype "bidirectional"))
    )
    (net (code "13") (name "LED-TOP") (class "Default")
      (node (ref "J8") (pin "P$5") (pinfunction "-5_P$5") (pintype "bidirectional"))
      (node (ref "U2") (pin "9") (pinfunction "PC1_9") (pintype "bidirectional"))
    )
    (net (code "14") (name "LED-UI") (class "Default")
      (node (ref "J9") (pin "2") (pinfunction "2_2") (pintype "passive"))
      (node (ref "U2") (pin "35") (pinfunction "PB14_35") (pintype "bidirectional"))
    )
    (net (code "15") (name "LED-WHITE") (class "Default")
      (node (ref "LED17") (pin "A") (pinfunction "A_A") (pintype "passive"))
      (node (ref "U2") (pin "33") (pinfunction "PB12_33") (pintype "bidirectional"))
    )
    (net (code "16") (name "NRST") (class "Default")
      (node (ref "C16") (pin "1") (pinfunction "1_1") (pintype "passive"))
      (node (ref "J13") (pin "P$3") (pinfunction "-3_P$3") (pintype "bidirectional"))
      (node (ref "R30") (pin "2") (pinfunction "2_2") (pintype "passive"))
      (node (ref "S1") (pin "1") (pinfunction "P_1") (pintype "passive"))
      (node (ref "U2") (pin "7") (pinfunction "NRST_7") (pintype "bidirectional"))
    )
    (net (code "17") (name "Net-(D3-C)") (class "Default")
      (node (ref "D3") (pin "K") (pinfunction "C_K") (pintype "passive"))
      (node (ref "X1") (pin "P$14") (pinfunction "5V_P$14") (pintype "bidirectional"))
    )
    (net (code "18") (name "Net-(IC1-+IN)") (class "Default")
      (node (ref "IC1") (pin "3") (pinfunction "+IN_3") (pintype "input"))
      (node (ref "R18") (pin "1") (pinfunction "1_1") (pintype "passive"))
      (node (ref "R20") (pin "2") (pinfunction "2_2") (pintype "passive"))
    )
    (net (code "19") (name "Net-(IC1--IN)") (class "Default")
      (node (ref "IC1") (pin "4") (pinfunction "-IN_4") (pintype "input"))
      (node (ref "R19") (pin "1") (pinfunction "1_1") (pintype "passive"))
      (node (ref "R21") (pin "2") (pinfunction "2_2") (pintype "passive"))
    )
    (net (code "20") (name "Net-(IC2-+IN)") (class "Default")
      (node (ref "IC2") (pin "3") (pinfunction "+IN_3") (pintype "input"))
      (node (ref "R22") (pin "1") (pinfunction "1_1") (pintype "passive"))
      (node (ref "R24") (pin "2") (pinfunction "2_2") (pintype "passive"))
    )
    (net (code "21") (name "Net-(IC2--IN)") (class "Default")
      (node (ref "IC2") (pin "4") (pinfunction "-IN_4") (pintype "input"))
      (node (ref "R23") (pin "1") (pinfunction "1_1") (pintype "passive"))
      (node (ref "R25") (pin "2") (pinfunction "2_2") (pintype "passive"))
    )
    (net (code "22") (name "Net-(J10-Pad3)") (class "Default")
      (node (ref "J10") (pin "3") (pinfunction "3_3") (pintype "passive"))
      (node (ref "R19") (pin "2") (pinfunction "2_2") (pintype "passive"))
    )
    (net (code "23") (name "Net-(J10-Pad4)") (class "Default")
      (node (ref "J10") (pin "4") (pinfunction "4_4") (pintype "passive"))
      (node (ref "R18") (pin "2") (pinfunction "2_2") (pintype "passive"))
    )
    (net (code "24") (name "Net-(J12-Pad3)") (class "Default")
      (node (ref "J12") (pin "3") (pinfunction "3_3") (pintype "passive"))
      (node (ref "R23") (pin "2") (pinfunction "2_2") (pintype "passive"))
    )
    (net (code "25") (name "Net-(J12-Pad4)") (class "Default")
      (node (ref "J12") (pin "4") (pinfunction "4_4") (pintype "passive"))
      (node (ref "R22") (pin "2") (pinfunction "2_2") (pintype "passive"))
    )
    (net (code "26") (name "Net-(LED1-DI)") (class "Default")
      (node (ref "JP1") (pin "2") (pinfunction "2_2") (pintype "passive"))
      (node (ref "LED1") (pin "3") (pinfunction "DI_3") (pintype "input"))
      (node (ref "R26") (pin "2") (pinfunction "2_2") (pintype "passive"))
      (node (ref "T2") (pin "1") (pinfunction "D_1") (pintype "passive"))
    )
    (net (code "27") (name "Net-(LED1-DO)") (class "Default")
      (node (ref "LED1") (pin "1") (pinfunction "DO_1") (pintype "output"))
      (node (ref "LED2") (pin "3") (pinfunction "DI_3") (pintype "input"))
    )
    (net (code "28") (name "Net-(LED2-DO)") (class "Default")
      (node (ref "LED2") (pin "1") (pinfunction "DO_1") (pintype "output"))
      (node (ref "LED3") (pin "3") (pinfunction "DI_3") (pintype "input"))
    )
    (net (code "29") (name "Net-(LED3-DO)") (class "Default")
      (node (ref "LED3") (pin "1") (pinfunction "DO_1") (pintype "output"))
      (node (ref "LED4") (pin "3") (pinfunction "DI_3") (pintype "input"))
    )
    (net (code "30") (name "Net-(LED4-DO)") (class "Default")
      (node (ref "LED4") (pin "1") (pinfunction "DO_1") (pintype "output"))
      (node (ref "LED5") (pin "3") (pinfunction "DI_3") (pintype "input"))
    )
    (net (code "31") (name "Net-(LED5-DO)") (class "Default")
      (node (ref "LED5") (pin "1") (pinfunction "DO_1") (pintype "output"))
      (node (ref "LED6") (pin "3") (pinfunction "DI_3") (pintype "input"))
    )
    (net (code "32") (name "Net-(LED6-DO)") (class "Default")
      (node (ref "LED6") (pin "1") (pinfunction "DO_1") (pintype "output"))
      (node (ref "LED7") (pin "3") (pinfunction "DI_3") (pintype "input"))
    )
    (net (code "33") (name "Net-(LED8-DI)") (class "Default")
      (node (ref "JP2") (pin "2") (pinfunction "2_2") (pintype "passive"))
      (node (ref "LED8") (pin "3") (pinfunction "DI_3") (pintype "input"))
      (node (ref "R28") (pin "2") (pinfunction "2_2") (pintype "passive"))
      (node (ref "T3") (pin "1") (pinfunction "D_1") (pintype "passive"))
    )
    (net (code "34") (name "Net-(LED8-DO)") (class "Default")
      (node (ref "LED8") (pin "1") (pinfunction "DO_1") (pintype "output"))
      (node (ref "LED9") (pin "3") (pinfunction "DI_3") (pintype "input"))
    )
    (net (code "35") (name "Net-(LED10-DI)") (class "Default")
      (node (ref "LED10") (pin "3") (pinfunction "DI_3") (pintype "input"))
      (node (ref "LED9") (pin "1") (pinfunction "DO_1") (pintype "output"))
    )
    (net (code "36") (name "Net-(LED10-DO)") (class "Default")
      (node (ref "LED10") (pin "1") (pinfunction "DO_1") (pintype "output"))
      (node (ref "LED11") (pin "3") (pinfunction "DI_3") (pintype "input"))
    )
    (net (code "37") (name "Net-(LED11-DO)") (class "Default")
      (node (ref "LED11") (pin "1") (pinfunction "DO_1") (pintype "output"))
      (node (ref "LED12") (pin "3") (pinfunction "DI_3") (pintype "input"))
    )
    (net (code "38") (name "Net-(LED12-DO)") (class "Default")
      (node (ref "LED12") (pin "1") (pinfunction "DO_1") (pintype "output"))
      (node (ref "LED13") (pin "3") (pinfunction "DI_3") (pintype "input"))
    )
    (net (code "39") (name "Net-(LED13-DO)") (class "Default")
      (node (ref "LED13") (pin "1") (pinfunction "DO_1") (pintype "output"))
      (node (ref "LED14") (pin "3") (pinfunction "DI_3") (pintype "input"))
    )
    (net (code "40") (name "Net-(LED15-PadA)") (class "Default")
      (node (ref "LED15") (pin "A") (pinfunction "A_A") (pintype "passive"))
      (node (ref "X2") (pin "A4B9") (pinfunction "VBUS_A4B9") (pintype "power_in"))
      (node (ref "X2") (pin "B4A9") (pinfunction "VBUS_B4A9") (pintype "power_in"))
    )
    (net (code "41") (name "Net-(LED15-PadC)") (class "Default")
      (node (ref "LED15") (pin "C") (pinfunction "C_C") (pintype "passive"))
      (node (ref "R3") (pin "2") (pinfunction "2_2") (pintype "passive"))
    )
    (net (code "42") (name "Net-(LED16-PadA)") (class "Default")
      (node (ref "LED16") (pin "A") (pinfunction "A_A") (pintype "passive"))
      (node (ref "X3") (pin "A4B9") (pinfunction "VBUS_A4B9") (pintype "power_in"))
      (node (ref "X3") (pin "B4A9") (pinfunction "VBUS_B4A9") (pintype "power_in"))
    )
    (net (code "43") (name "Net-(LED16-PadC)") (class "Default")
      (node (ref "LED16") (pin "C") (pinfunction "C_C") (pintype "passive"))
      (node (ref "R9") (pin "2") (pinfunction "2_2") (pintype "passive"))
    )
    (net (code "44") (name "Net-(LED17-PadC)") (class "Default")
      (node (ref "LED17") (pin "C") (pinfunction "C_C") (pintype "passive"))
      (node (ref "R32") (pin "2") (pinfunction "2_2") (pintype "passive"))
    )
    (net (code "45") (name "Net-(LED18-PadA)") (class "Default")
      (node (ref "LED18") (pin "A") (pinfunction "A_A") (pintype "passive"))
      (node (ref "R10") (pin "1") (pinfunction "1_1") (pintype "passive"))
    )
    (net (code "46") (name "Net-(Q1-B)") (class "Default")
      (node (ref "Q1") (pin "1") (pinfunction "B_1") (pintype "passive"))
      (node (ref "R17") (pin "1") (pinfunction "1_1") (pintype "passive"))
    )
    (net (code "47") (name "Net-(T1-D)") (class "Default")
      (node (ref "LS1") (pin "2") (pinfunction "2_2") (pintype "passive"))
      (node (ref "T1") (pin "1") (pinfunction "D_1") (pintype "passive"))
    )
    (net (code "48") (name "Net-(U1-TNOW)") (class "Default")
      (node (ref "R10") (pin "2") (pinfunction "2_2") (pintype "passive"))
      (node (ref "U1") (pin "6") (pinfunction "TNOW_6") (pintype "output"))
    )
    (net (code "49") (name "Net-(U1-V3)") (class "Default")
      (node (ref "C14") (pin "1") (pinfunction "1_1") (pintype "passive"))
      (node (ref "U1") (pin "10") (pinfunction "V3_10") (pintype "power_in"))
    )
    (net (code "50") (name "Net-(U2B-VCAP_1)") (class "Default")
      (node (ref "C1") (pin "1") (pinfunction "1_1") (pintype "passive"))
      (node (ref "U2") (pin "30") (pinfunction "VCAP_1_30") (pintype "power_in"))
    )
    (net (code "51") (name "Net-(U5-B)") (class "Default")
      (node (ref "R15") (pin "2") (pinfunction "2_2") (pintype "passive"))
      (node (ref "R16") (pin "1") (pinfunction "1_1") (pintype "passive"))
      (node (ref "U5") (pin "7") (pinfunction "B_7") (pintype "bidirectional"))
    )
    (net (code "52") (name "Net-(X2-CC1)") (class "Default")
      (node (ref "R1") (pin "1") (pinfunction "1_1") (pintype "passive"))
      (node (ref "X2") (pin "A5") (pinfunction "CC1_A5") (pintype "bidirectional"))
    )
    (net (code "53") (name "Net-(X2-CC2)") (class "Default")
      (node (ref "R2") (pin "1") (pinfunction "1_1") (pintype "passive"))
      (node (ref "X2") (pin "B5") (pinfunction "CC2_B5") (pintype "bidirectional"))
    )
    (net (code "54") (name "Net-(X3-CC1)") (class "Default")
      (node (ref "R7") (pin "1") (pinfunction "1_1") (pintype "passive"))
      (node (ref "X3") (pin "A5") (pinfunction "CC1_A5") (pintype "bidirectional"))
    )
    (net (code "55") (name "Net-(X3-CC2)") (class "Default")
      (node (ref "R8") (pin "1") (pinfunction "1_1") (pintype "passive"))
      (node (ref "X3") (pin "B5") (pinfunction "CC2_B5") (pintype "bidirectional"))
    )
    (net (code "56") (name "RTS") (class "Default")
      (node (ref "U1") (pin "4") (pinfunction "RTS_4") (pintype "output"))
    )
    (net (code "57") (name "SCL") (class "Default")
      (node (ref "R13") (pin "2") (pinfunction "2_2") (pintype "passive"))
      (node (ref "U2") (pin "61") (pinfunction "PB8_61") (pintype "bidirectional"))
      (node (ref "U4") (pin "4") (pinfunction "SCL_4") (pintype "bidirectional"))
    )
    (net (code "58") (name "SDA") (class "Default")
      (node (ref "R12") (pin "2") (pinfunction "2_2") (pintype "passive"))
      (node (ref "U2") (pin "62") (pinfunction "PB9_62") (pintype "bidirectional"))
      (node (ref "U4") (pin "3") (pinfunction "SDA_3") (pintype "bidirectional"))
    )
    (net (code "59") (name "SERVO-SIG") (class "Default")
      (node (ref "J3") (pin "1") (pinfunction "1_1") (pintype "passive"))
      (node (ref "J4") (pin "1") (pinfunction "1_1") (pintype "passive"))
      (node (ref "J5") (pin "1") (pinfunction "1_1") (pintype "passive"))
      (node (ref "J6") (pin "1") (pinfunction "1_1") (pintype "passive"))
      (node (ref "J7") (pin "1") (pinfunction "1_1") (pintype "passive"))
      (node (ref "U5") (pin "6") (pinfunction "A_6") (pintype "bidirectional"))
    )
    (net (code "60") (name "SIG-FLOOR") (class "Default")
      (node (ref "J11") (pin "3") (pinfunction "3_3") (pintype "passive"))
      (node (ref "R11") (pin "2") (pinfunction "2_2") (pintype "passive"))
      (node (ref "U2") (pin "8") (pinfunction "PC0_8") (pintype "bidirectional"))
    )
    (net (code "61") (name "SPK") (class "Default")
      (node (ref "T1") (pin "3") (pinfunction "G_3") (pintype "passive"))
      (node (ref "U2") (pin "58") (pinfunction "PB6_58") (pintype "bidirectional"))
    )
    (net (code "62") (name "SW1") (class "Default")
      (node (ref "J9") (pin "4") (pinfunction "4_4") (pintype "passive"))
      (node (ref "R5") (pin "2") (pinfunction "2_2") (pintype "passive"))
      (node (ref "U2") (pin "20") (pinfunction "PA4_20") (pintype "bidirectional"))
    )
    (net (code "63") (name "SW2") (class "Default")
      (node (ref "J9") (pin "3") (pinfunction "3_3") (pintype "passive"))
      (node (ref "R6") (pin "2") (pinfunction "2_2") (pintype "passive"))
      (node (ref "U2") (pin "21") (pinfunction "PA5_21") (pintype "bidirectional"))
    )
    (net (code "64") (name "SWCLK") (class "Default")
      (node (ref "J13") (pin "P$1") (pinfunction "-1_P$1") (pintype "bidirectional"))
      (node (ref "U2") (pin "49") (pinfunction "PA14_49") (pintype "bidirectional"))
    )
    (net (code "65") (name "SWDIO") (class "Default")
      (node (ref "J13") (pin "P$2") (pinfunction "-2_P$2") (pintype "bidirectional"))
      (node (ref "U2") (pin "46") (pinfunction "PA13_46") (pintype "bidirectional"))
    )
    (net (code "66") (name "SWO") (class "Default")
      (node (ref "U2") (pin "55") (pinfunction "PB3_55") (pintype "bidirectional"))
    )
    (net (code "67") (name "TOGGLE") (class "Default")
      (node (ref "J9") (pin "1") (pinfunction "1_1") (pintype "passive"))
      (node (ref "R4") (pin "2") (pinfunction "2_2") (pintype "passive"))
      (node (ref "U2") (pin "22") (pinfunction "PA6_22") (pintype "bidirectional"))
    )
    (net (code "68") (name "UART1-RX") (class "Default")
      (node (ref "U1") (pin "8") (pinfunction "TX_8") (pintype "output"))
      (node (ref "U2") (pin "43") (pinfunction "PA10_43") (pintype "bidirectional"))
    )
    (net (code "69") (name "UART1-TX") (class "Default")
      (node (ref "U1") (pin "9") (pinfunction "RX_9") (pintype "input"))
      (node (ref "U2") (pin "42") (pinfunction "PA9_42") (pintype "bidirectional"))
    )
    (net (code "70") (name "UART2-RX") (class "Default")
      (node (ref "J2") (pin "P$4") (pinfunction "-4_P$4") (pintype "bidirectional"))
      (node (ref "U2") (pin "17") (pinfunction "PA3_17") (pintype "bidirectional"))
    )
    (net (code "71") (name "UART2-TX") (class "Default")
      (node (ref "J2") (pin "P$3") (pinfunction "-3_P$3") (pintype "bidirectional"))
      (node (ref "U2") (pin "16") (pinfunction "PA2_16") (pintype "bidirectional"))
    )
    (net (code "72") (name "UART3-RX") (class "Default")
      (node (ref "U2") (pin "25") (pinfunction "PC5_25") (pintype "bidirectional"))
      (node (ref "X1") (pin "P$7") (pinfunction "PB08_A6_D6_TX_P$7") (pintype "bidirectional"))
    )
    (net (code "73") (name "UART3-TX") (class "Default")
      (node (ref "U2") (pin "29") (pinfunction "PB10_29") (pintype "bidirectional"))
      (node (ref "X1") (pin "P$8") (pinfunction "PB09_A7_D7_RX_P$8") (pintype "bidirectional"))
    )
    (net (code "74") (name "UART4-RX") (class "Default")
      (node (ref "J8") (pin "P$4") (pinfunction "-4_P$4") (pintype "bidirectional"))
      (node (ref "U2") (pin "15") (pinfunction "PA1_15") (pintype "bidirectional"))
    )
    (net (code "75") (name "UART4-TX") (class "Default")
      (node (ref "J8") (pin "P$3") (pinfunction "-3_P$3") (pintype "bidirectional"))
      (node (ref "U2") (pin "14") (pinfunction "PA0_14") (pintype "bidirectional"))
    )
    (net (code "76") (name "UART5-RX") (class "Default")
      (node (ref "U2") (pin "54") (pinfunction "PD2_54") (pintype "bidirectional"))
      (node (ref "U5") (pin "1") (pinfunction "RO_1") (pintype "output"))
    )
    (net (code "77") (name "UART5-TX") (class "Default")
      (node (ref "R17") (pin "2") (pinfunction "2_2") (pintype "passive"))
      (node (ref "U2") (pin "53") (pinfunction "PC12_53") (pintype "bidirectional"))
      (node (ref "U5") (pin "4") (pinfunction "DI_4") (pintype "input"))
    )
    (net (code "78") (name "UART6-RX") (class "Default")
      (node (ref "J1") (pin "P$4") (pinfunction "-4_P$4") (pintype "bidirectional"))
      (node (ref "U2") (pin "38") (pinfunction "PC7_38") (pintype "bidirectional"))
    )
    (net (code "79") (name "UART6-TX") (class "Default")
      (node (ref "J1") (pin "P$3") (pinfunction "-3_P$3") (pintype "bidirectional"))
      (node (ref "U2") (pin "37") (pinfunction "PC6_37") (pintype "bidirectional"))
    )
    (net (code "80") (name "VDD") (class "Default")
      (node (ref "C10") (pin "+") (pinfunction "+_+") (pintype "passive"))
      (node (ref "C12") (pin "+") (pinfunction "+_+") (pintype "passive"))
      (node (ref "C13") (pin "+") (pinfunction "+_+") (pintype "passive"))
      (node (ref "C15") (pin "+") (pinfunction "+_+") (pintype "passive"))
      (node (ref "C8") (pin "1") (pinfunction "1_1") (pintype "passive"))
      (node (ref "C9") (pin "+") (pinfunction "+_+") (pintype "passive"))
      (node (ref "D1") (pin "K") (pinfunction "C_K") (pintype "passive"))
      (node (ref "D2") (pin "K") (pinfunction "C_K") (pintype "passive"))
      (node (ref "J3") (pin "3") (pinfunction "3_3") (pintype "passive"))
      (node (ref "J4") (pin "3") (pinfunction "3_3") (pintype "passive"))
      (node (ref "J5") (pin "3") (pinfunction "3_3") (pintype "passive"))
      (node (ref "J6") (pin "3") (pinfunction "3_3") (pintype "passive"))
      (node (ref "J7") (pin "3") (pinfunction "3_3") (pintype "passive"))
      (node (ref "J8") (pin "P$1") (pinfunction "-1_P$1") (pintype "bidirectional"))
      (node (ref "REG1") (pin "1") (pinfunction "VIN_1") (pintype "passive"))
      (node (ref "REG2") (pin "1") (pinfunction "VIN_1") (pintype "passive"))
      (node (ref "XT1") (pin "1") (pinfunction "1_1") (pintype "passive"))
    )
    (net (code "81") (name "VOUT") (class "Default")
      (node (ref "U4") (pin "8") (pinfunction "VOUT_8") (pintype "power_in"))
    )
    (net (code "82") (name "unconnected-(LED7-DO-Pad1)") (class "Default")
      (node (ref "LED7") (pin "1") (pinfunction "DO_1") (pintype "output"))
    )
    (net (code "83") (name "unconnected-(LED14-DO-Pad1)") (class "Default")
      (node (ref "LED14") (pin "1") (pinfunction "DO_1") (pintype "output"))
    )
    (net (code "84") (name "unconnected-(SW1-S-Pad2)") (class "Default")
      (node (ref "SW1") (pin "2") (pinfunction "S_2") (pintype "passive"))
    )
    (net (code "85") (name "unconnected-(U2A-PA7-Pad23)") (class "Default")
      (node (ref "U2") (pin "23") (pinfunction "PA7_23") (pintype "bidirectional"))
    )
    (net (code "86") (name "unconnected-(U2A-PA8-Pad41)") (class "Default")
      (node (ref "U2") (pin "41") (pinfunction "PA8_41") (pintype "bidirectional"))
    )
    (net (code "87") (name "unconnected-(U2A-PA11-Pad44)") (class "Default")
      (node (ref "U2") (pin "44") (pinfunction "PA11_44") (pintype "bidirectional"))
    )
    (net (code "88") (name "unconnected-(U2A-PA12-Pad45)") (class "Default")
      (node (ref "U2") (pin "45") (pinfunction "PA12_45") (pintype "bidirectional"))
    )
    (net (code "89") (name "unconnected-(U2A-PB0-Pad26)") (class "Default")
      (node (ref "U2") (pin "26") (pinfunction "PB0_26") (pintype "bidirectional"))
    )
    (net (code "90") (name "unconnected-(U2A-PB1-Pad27)") (class "Default")
      (node (ref "U2") (pin "27") (pinfunction "PB1_27") (pintype "bidirectional"))
    )
    (net (code "91") (name "unconnected-(U2A-PB2-Pad28)") (class "Default")
      (node (ref "U2") (pin "28") (pinfunction "PB2_28") (pintype "bidirectional"))
    )
    (net (code "92") (name "unconnected-(U2A-PB4-Pad56)") (class "Default")
      (node (ref "U2") (pin "56") (pinfunction "PB4_56") (pintype "bidirectional"))
    )
    (net (code "93") (name "unconnected-(U2A-PB5-Pad57)") (class "Default")
      (node (ref "U2") (pin "57") (pinfunction "PB5_57") (pintype "bidirectional"))
    )
    (net (code "94") (name "unconnected-(U2A-PB7-Pad59)") (class "Default")
      (node (ref "U2") (pin "59") (pinfunction "PB7_59") (pintype "bidirectional"))
    )
    (net (code "95") (name "unconnected-(U2A-PC2-Pad10)") (class "Default")
      (node (ref "U2") (pin "10") (pinfunction "PC2_10") (pintype "bidirectional"))
    )
    (net (code "96") (name "unconnected-(U2A-PC3-Pad11)") (class "Default")
      (node (ref "U2") (pin "11") (pinfunction "PC3_11") (pintype "bidirectional"))
    )
    (net (code "97") (name "unconnected-(U2A-PC4-Pad24)") (class "Default")
      (node (ref "U2") (pin "24") (pinfunction "PC4_24") (pintype "bidirectional"))
    )
    (net (code "98") (name "unconnected-(U2A-PC8-Pad39)") (class "Default")
      (node (ref "U2") (pin "39") (pinfunction "PC8_39") (pintype "bidirectional"))
    )
    (net (code "99") (name "unconnected-(U2A-PC9-Pad40)") (class "Default")
      (node (ref "U2") (pin "40") (pinfunction "PC9_40") (pintype "bidirectional"))
    )
    (net (code "100") (name "unconnected-(U2A-PC10-Pad51)") (class "Default")
      (node (ref "U2") (pin "51") (pinfunction "PC10_51") (pintype "bidirectional"))
    )
    (net (code "101") (name "unconnected-(U2A-PC11-Pad52)") (class "Default")
      (node (ref "U2") (pin "52") (pinfunction "PC11_52") (pintype "bidirectional"))
    )
    (net (code "102") (name "unconnected-(U2A-PC13-Pad2)") (class "Default")
      (node (ref "U2") (pin "2") (pinfunction "PC13_2") (pintype "bidirectional"))
    )
    (net (code "103") (name "unconnected-(U2A-PC14-OSC32_IN-Pad3)") (class "Default")
      (node (ref "U2") (pin "3") (pinfunction "PC14-OSC32_IN_3") (pintype "bidirectional"))
    )
    (net (code "104") (name "unconnected-(U2A-PC15-OSC32_OUT-Pad4)") (class "Default")
      (node (ref "U2") (pin "4") (pinfunction "PC15-OSC32_OUT_4") (pintype "bidirectional"))
    )
    (net (code "105") (name "unconnected-(U2A-PH0-OSC_IN-Pad5)") (class "Default")
      (node (ref "U2") (pin "5") (pinfunction "PH0-OSC_IN_5") (pintype "bidirectional"))
    )
    (net (code "106") (name "unconnected-(U2A-PH1-Pad6)") (class "Default")
      (node (ref "U2") (pin "6") (pinfunction "PH1_6") (pintype "bidirectional"))
    )
    (net (code "107") (name "unconnected-(U4-INT-Pad6)") (class "Default")
      (node (ref "U4") (pin "6") (pinfunction "INT_6") (pintype "bidirectional"))
    )
    (net (code "108") (name "unconnected-(U4-RST-Pad5)") (class "Default")
      (node (ref "U4") (pin "5") (pinfunction "RST_5") (pintype "bidirectional"))
    )
    (net (code "109") (name "unconnected-(X1-3V3-PadP$12)") (class "Default")
      (node (ref "X1") (pin "P$12") (pinfunction "3V3_P$12") (pintype "bidirectional"))
    )
    (net (code "110") (name "unconnected-(X1-PA02_A0_D0-PadP$1)") (class "Default")
      (node (ref "X1") (pin "P$1") (pinfunction "PA02_A0_D0_P$1") (pintype "bidirectional"))
    )
    (net (code "111") (name "unconnected-(X1-PA4_A1_D1-PadP$2)") (class "Default")
      (node (ref "X1") (pin "P$2") (pinfunction "PA4_A1_D1_P$2") (pintype "bidirectional"))
    )
    (net (code "112") (name "unconnected-(X1-PA5_A9_D9_MISO-PadP$10)") (class "Default")
      (node (ref "X1") (pin "P$10") (pinfunction "PA5_A9_D9_MISO_P$10") (pintype "bidirectional"))
    )
    (net (code "113") (name "unconnected-(X1-PA6_A10_D10_MOSI-PadP$11)") (class "Default")
      (node (ref "X1") (pin "P$11") (pinfunction "PA6_A10_D10_MOSI_P$11") (pintype "bidirectional"))
    )
    (net (code "114") (name "unconnected-(X1-PA7_A8_D8_SCK-PadP$9)") (class "Default")
      (node (ref "X1") (pin "P$9") (pinfunction "PA7_A8_D8_SCK_P$9") (pintype "bidirectional"))
    )
    (net (code "115") (name "unconnected-(X1-PA8_A4_D4_SDA-PadP$5)") (class "Default")
      (node (ref "X1") (pin "P$5") (pinfunction "PA8_A4_D4_SDA_P$5") (pintype "bidirectional"))
    )
    (net (code "116") (name "unconnected-(X1-PA9_A5_D5_SCL-PadP$6)") (class "Default")
      (node (ref "X1") (pin "P$6") (pinfunction "PA9_A5_D5_SCL_P$6") (pintype "bidirectional"))
    )
    (net (code "117") (name "unconnected-(X1-PA10_A2_D2-PadP$3)") (class "Default")
      (node (ref "X1") (pin "P$3") (pinfunction "PA10_A2_D2_P$3") (pintype "bidirectional"))
    )
    (net (code "118") (name "unconnected-(X1-PA11_A3_D3-PadP$4)") (class "Default")
      (node (ref "X1") (pin "P$4") (pinfunction "PA11_A3_D3_P$4") (pintype "bidirectional"))
    )
    (net (code "119") (name "unconnected-(X2-SBU1-PadA8)") (class "Default")
      (node (ref "X2") (pin "A8") (pinfunction "SBU1_A8") (pintype "bidirectional"))
    )
    (net (code "120") (name "unconnected-(X2-SBU2-PadB8)") (class "Default")
      (node (ref "X2") (pin "B8") (pinfunction "SBU2_B8") (pintype "bidirectional"))
    )
    (net (code "121") (name "unconnected-(X3-SBU1-PadA8)") (class "Default")
      (node (ref "X3") (pin "A8") (pinfunction "SBU1_A8") (pintype "bidirectional"))
    )
    (net (code "122") (name "unconnected-(X3-SBU2-PadB8)") (class "Default")
      (node (ref "X3") (pin "B8") (pinfunction "SBU2_B8") (pintype "bidirectional"))
    )
    (net (code "123") (name "~{RE}") (class "Default")
      (node (ref "Q1") (pin "3") (pinfunction "C_3") (pintype "passive"))
      (node (ref "R14") (pin "1") (pinfunction "1_1") (pintype "passive"))
      (node (ref "U5") (pin "2") (pinfunction "~{RE}_2") (pintype "input"))
      (node (ref "U5") (pin "3") (pinfunction "DE_3") (pintype "input"))
    )
  )
)
